# General.net
KiCad netlist of a schematic drawn in Altium Designer
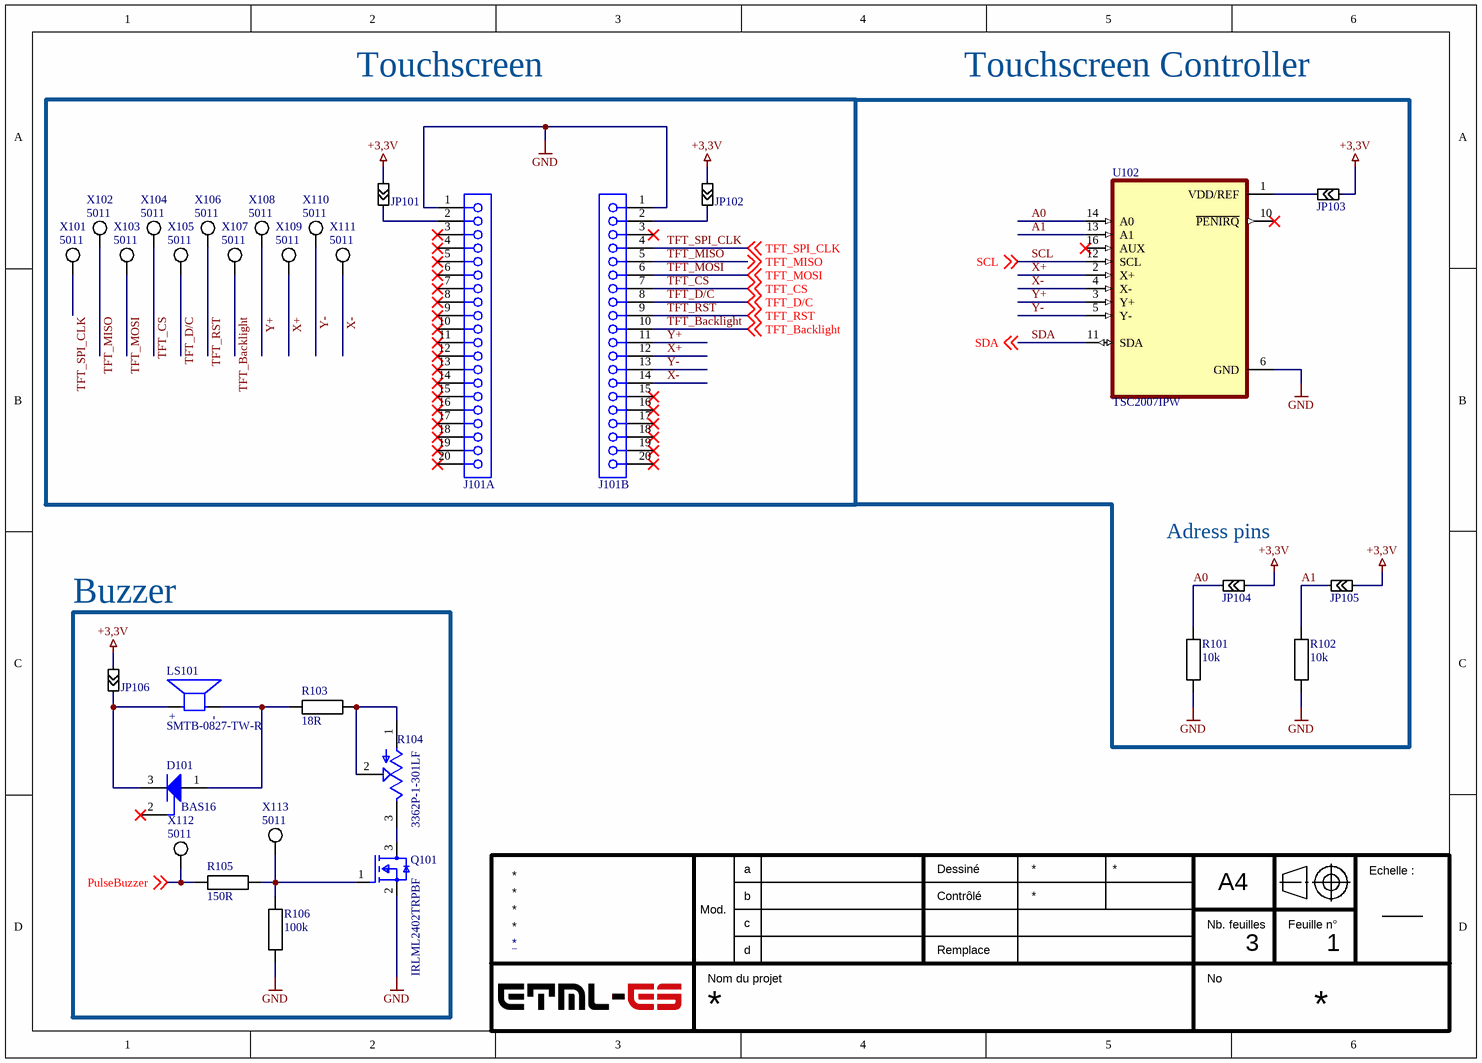
[diagram p0: General.SchDoc]

(export (version "E")
  (design (tool "Eeschema 10.0.6"))
  (components
    (comp (ref "D101")
      (value "BAS16")
      (footprint "INF-SOT23_L")
      (description "Silicon Switching Diode, SOT23, Reel, Green")
      (fields (field (name "MANUFACTURER") "Infineon"))
      (libsource (lib "Altium Content Vault") (part "INF-D_A1K3-3"))
    )
    (comp (ref "J101A")
      (value "61302011821")
      (footprint "61302011821")
      (description "WR-PHD Socket Header, THT, Vertical, pitch 2.54mm, 1 Row, 20P")
      (fields (field (name "MANUFACTURER") "Wurth Elektronik"))
      (libsource (lib "2318_Métronome_Electronique_Library") (part "61302011821"))
    )
    (comp (ref "J101B")
      (value "61302011821")
      (footprint "61302011821")
      (description "WR-PHD Socket Header, THT, Vertical, pitch 2.54mm, 1 Row, 20P")
      (fields (field (name "MANUFACTURER") "Wurth Elektronik"))
      (libsource (lib "2318_Métronome_Electronique_Library") (part "61302011821"))
    )
    (comp (ref "JP101")
      (value "Jumper Pad")
      (footprint "Jumper SMD")
      (description "SMD Jumper")
      (libsource (lib "2318_Métronome_Electronique_Library") (part "Jumper Pad"))
    )
    (comp (ref "JP102")
      (value "Jumper Pad")
      (footprint "Jumper SMD")
      (description "SMD Jumper")
      (libsource (lib "2318_Métronome_Electronique_Library") (part "Jumper Pad"))
    )
    (comp (ref "JP103")
      (value "Jumper Pad")
      (footprint "Jumper SMD")
      (description "SMD Jumper")
      (libsource (lib "2318_Métronome_Electronique_Library") (part "Jumper Pad"))
    )
    (comp (ref "JP104")
      (value "Jumper Pad")
      (footprint "Jumper SMD")
      (description "SMD Jumper")
      (libsource (lib "2318_Métronome_Electronique_Library") (part "Jumper Pad"))
    )
    (comp (ref "JP105")
      (value "Jumper Pad")
      (footprint "Jumper SMD")
      (description "SMD Jumper")
      (libsource (lib "2318_Métronome_Electronique_Library") (part "Jumper Pad"))
    )
    (comp (ref "JP106")
      (value "Jumper Pad")
      (footprint "Jumper SMD")
      (description "SMD Jumper")
      (libsource (lib "2318_Métronome_Electronique_Library") (part "Jumper Pad"))
    )
    (comp (ref "LS101")
      (value "SMTB-0827-TW-R")
      (footprint "XDCR_SMTB-0827-TW-R")
      (description "SURFACE MOUNT TRANSDUCER 3.6 V0-P")
      (fields
        (field (name "DIGI-KEY_PART_NUMBER") "668-SMTB-0827-TW-RTR-ND")
        (field (name "MF") "PUI Audio, Inc.")
      )
      (libsource (lib "2318_Métronome_Electronique_Library") (part "SMTB-0827-TW-R"))
    )
    (comp (ref "Q101")
      (value "IRLML2402TRPBF")
      (footprint "SOT95P237X112-3N")
      (description "MOSFET N-CH 20V 1.2A SOT-23")
      (libsource (lib "2318_Métronome_Electronique_Library") (part "IRLML2402TRPBF"))
    )
    (comp (ref "R101")
      (value "10k")
      (footprint "RESC2012X06M")
      (description "RES 10kohm  ±1% 0.125W 2012 (0805 INCH)")
      (fields (field (name "TOLERANCE") "±1%") (field (name "VOLTAGE") "150V"))
      (libsource (lib "ETML-ES") (part "RES"))
    )
    (comp (ref "R102")
      (value "10k")
      (footprint "RESC2012X06M")
      (description "RES 10kohm  ±1% 0.125W 2012 (0805 INCH)")
      (fields (field (name "TOLERANCE") "±1%") (field (name "VOLTAGE") "150V"))
      (libsource (lib "ETML-ES") (part "RES"))
    )
    (comp (ref "R103")
      (value "18R")
      (footprint "RESC2012X06M")
      (description "RES 18ohm  ±1% 0.125W 2012 (0805 INCH)")
      (fields (field (name "POWER") "0.125W") (field (name "TOLERANCE") "±1%"))
      (libsource (lib "ETML-ES") (part "RES"))
    )
    (comp (ref "R104")
      (value "3362P-1-301LF")
      (footprint "TRIM_3362P-1-301LF")
      (description "300 Ohms 0.5W, 1/2W PC Pins Through Hole Trimmer Potentiometer Cermet 1 Turn Top Adjustment")
      (fields (field (name "MF") "Bourns"))
      (libsource (lib "2318_Métronome_Electronique_Library") (part "3362P-1-301LF"))
    )
    (comp (ref "R105")
      (value "150R")
      (footprint "RESC2012X06M")
      (description "RES 150ohm  ±1% 0.125W 2012 (0805 INCH)")
      (fields (field (name "MANUFACTURER") "Yageo") (field (name "TOLERANCE") "±1%"))
      (libsource (lib "ETML-ES") (part "RES"))
    )
    (comp (ref "R106")
      (value "100k")
      (footprint "RESC2012X06M")
      (description "RES 100kohm  ±1% 0.125W 2012 (0805 INCH)")
      (fields (field (name "MANUFACTURER") "Yageo") (field (name "VOLTAGE") "150V"))
      (libsource (lib "ETML-ES") (part "RES"))
    )
    (comp (ref "U102")
      (value "TSC2007IPW")
      (footprint "SOP65P640X120-16N")
      (description "12-Bit, nanopower, 4-wire micro touch screen controller &nbsp; 16-TSSOP -40 to 85")
      (fields (field (name "DIGI-KEY_PART_NUMBER") "296-42398-2-ND") (field (name "MF") "Texas Instruments"))
      (libsource (lib "2318_Métronome_Electronique_Library") (part "TSC2007IPW"))
    )
    (comp (ref "X101")
      (value "5011")
      (footprint "Keystone_5011")
      (description "TEST THT MULTIPURPOSE BK")
      (fields (field (name "MANUFACTURER") "Keystone"))
      (libsource (lib "ETML-ES") (part "TEST"))
    )
    (comp (ref "X102")
      (value "5011")
      (footprint "Keystone_5011")
      (description "TEST THT MULTIPURPOSE BK")
      (fields (field (name "MANUFACTURER") "Keystone"))
      (libsource (lib "ETML-ES") (part "TEST"))
    )
    (comp (ref "X103")
      (value "5011")
      (footprint "Keystone_5011")
      (description "TEST THT MULTIPURPOSE BK")
      (fields (field (name "MANUFACTURER") "Keystone"))
      (libsource (lib "ETML-ES") (part "TEST"))
    )
    (comp (ref "X104")
      (value "5011")
      (footprint "Keystone_5011")
      (description "TEST THT MULTIPURPOSE BK")
      (fields (field (name "MANUFACTURER") "Keystone"))
      (libsource (lib "ETML-ES") (part "TEST"))
    )
    (comp (ref "X105")
      (value "5011")
      (footprint "Keystone_5011")
      (description "TEST THT MULTIPURPOSE BK")
      (fields (field (name "MANUFACTURER") "Keystone"))
      (libsource (lib "ETML-ES") (part "TEST"))
    )
    (comp (ref "X106")
      (value "5011")
      (footprint "Keystone_5011")
      (description "TEST THT MULTIPURPOSE BK")
      (fields (field (name "MANUFACTURER") "Keystone"))
      (libsource (lib "ETML-ES") (part "TEST"))
    )
    (comp (ref "X107")
      (value "5011")
      (footprint "Keystone_5011")
      (description "TEST THT MULTIPURPOSE BK")
      (fields (field (name "MANUFACTURER") "Keystone"))
      (libsource (lib "ETML-ES") (part "TEST"))
    )
    (comp (ref "X108")
      (value "5011")
      (footprint "Keystone_5011")
      (description "TEST THT MULTIPURPOSE BK")
      (fields (field (name "MANUFACTURER") "Keystone"))
      (libsource (lib "ETML-ES") (part "TEST"))
    )
    (comp (ref "X109")
      (value "5011")
      (footprint "Keystone_5011")
      (description "TEST THT MULTIPURPOSE BK")
      (fields (field (name "MANUFACTURER") "Keystone"))
      (libsource (lib "ETML-ES") (part "TEST"))
    )
    (comp (ref "X110")
      (value "5011")
      (footprint "Keystone_5011")
      (description "TEST THT MULTIPURPOSE BK")
      (fields (field (name "MANUFACTURER") "Keystone"))
      (libsource (lib "ETML-ES") (part "TEST"))
    )
    (comp (ref "X111")
      (value "5011")
      (footprint "Keystone_5011")
      (description "TEST THT MULTIPURPOSE BK")
      (fields (field (name "MANUFACTURER") "Keystone"))
      (libsource (lib "ETML-ES") (part "TEST"))
    )
    (comp (ref "X112")
      (value "5011")
      (footprint "Keystone_5011")
      (description "TEST THT MULTIPURPOSE BK")
      (fields (field (name "MANUFACTURER") "Keystone"))
      (libsource (lib "ETML-ES") (part "TEST"))
    )
    (comp (ref "X113")
      (value "5011")
      (footprint "Keystone_5011")
      (description "TEST THT MULTIPURPOSE BK")
      (fields (field (name "MANUFACTURER") "Keystone"))
      (libsource (lib "ETML-ES") (part "TEST"))
    )
  )
  (nets
    (net (code "1") (name "+3,3V") (class "Default")
      (node (ref "JP101") (pin "2") (pinfunction "2_2") (pintype "passive"))
      (node (ref "JP102") (pin "2") (pinfunction "2_2") (pintype "passive"))
      (node (ref "JP103") (pin "2") (pinfunction "2_2") (pintype "passive"))
      (node (ref "JP104") (pin "2") (pinfunction "2_2") (pintype "passive"))
      (node (ref "JP105") (pin "2") (pinfunction "2_2") (pintype "passive"))
      (node (ref "JP106") (pin "2") (pinfunction "2_2") (pintype "passive"))
    )
    (net (code "2") (name "/A0") (class "Default")
      (node (ref "JP104") (pin "1") (pinfunction "1_1") (pintype "passive"))
      (node (ref "R101") (pin "2") (pinfunction "2_2") (pintype "passive"))
      (node (ref "U102") (pin "14") (pinfunction "A0_14") (pintype "input"))
    )
    (net (code "3") (name "/A1") (class "Default")
      (node (ref "JP105") (pin "1") (pinfunction "1_1") (pintype "passive"))
      (node (ref "R102") (pin "2") (pinfunction "2_2") (pintype "passive"))
      (node (ref "U102") (pin "13") (pinfunction "A1_13") (pintype "input"))
    )
    (net (code "4") (name "/X+") (class "Default")
      (node (ref "J101B") (pin "12") (pinfunction "12_12") (pintype "passive"))
      (node (ref "U102") (pin "2") (pinfunction "X+_2") (pintype "input"))
      (node (ref "X109") (pin "1") (pinfunction "TP_1") (pintype "passive"))
    )
    (net (code "5") (name "/X-") (class "Default")
      (node (ref "J101B") (pin "14") (pinfunction "14_14") (pintype "passive"))
      (node (ref "U102") (pin "4") (pinfunction "X-_4") (pintype "input"))
      (node (ref "X111") (pin "1") (pinfunction "TP_1") (pintype "passive"))
    )
    (net (code "6") (name "/Y+") (class "Default")
      (node (ref "J101B") (pin "11") (pinfunction "11_11") (pintype "passive"))
      (node (ref "U102") (pin "3") (pinfunction "Y+_3") (pintype "input"))
      (node (ref "X108") (pin "1") (pinfunction "TP_1") (pintype "passive"))
    )
    (net (code "7") (name "/Y-") (class "Default")
      (node (ref "J101B") (pin "13") (pinfunction "13_13") (pintype "passive"))
      (node (ref "U102") (pin "5") (pinfunction "Y-_5") (pintype "input"))
      (node (ref "X110") (pin "1") (pinfunction "TP_1") (pintype "passive"))
    )
    (net (code "8") (name "GND") (class "Default")
      (node (ref "J101A") (pin "1") (pinfunction "1_1") (pintype "passive"))
      (node (ref "J101B") (pin "1") (pinfunction "1_1") (pintype "passive"))
      (node (ref "Q101") (pin "2") (pinfunction "S_2") (pintype "passive"))
      (node (ref "R101") (pin "1") (pinfunction "1_1") (pintype "passive"))
      (node (ref "R102") (pin "1") (pinfunction "1_1") (pintype "passive"))
      (node (ref "R106") (pin "1") (pinfunction "1_1") (pintype "passive"))
      (node (ref "U102") (pin "6") (pinfunction "GND_6") (pintype "power_in"))
    )
    (net (code "9") (name "Net-(D101-A)") (class "Default")
      (node (ref "D101") (pin "1") (pinfunction "A_1") (pintype "passive"))
      (node (ref "LS101") (pin "N") (pinfunction "NEG_N") (pintype "passive"))
      (node (ref "R103") (pin "2") (pinfunction "2_2") (pintype "passive"))
    )
    (net (code "10") (name "Net-(D101-K)") (class "Default")
      (node (ref "D101") (pin "3") (pinfunction "K_3") (pintype "passive"))
      (node (ref "JP106") (pin "1") (pinfunction "1_1") (pintype "passive"))
      (node (ref "LS101") (pin "P") (pinfunction "POS_P") (pintype "passive"))
    )
    (net (code "11") (name "Net-(J101A-Pad2)") (class "Default")
      (node (ref "J101A") (pin "2") (pinfunction "2_2") (pintype "passive"))
      (node (ref "JP101") (pin "1") (pinfunction "1_1") (pintype "passive"))
    )
    (net (code "12") (name "Net-(J101B-Pad2)") (class "Default")
      (node (ref "J101B") (pin "2") (pinfunction "2_2") (pintype "passive"))
      (node (ref "JP102") (pin "1") (pinfunction "1_1") (pintype "passive"))
    )
    (net (code "13") (name "Net-(Q101-D)") (class "Default")
      (node (ref "Q101") (pin "3") (pinfunction "D_3") (pintype "passive"))
      (node (ref "R104") (pin "3") (pinfunction "CW_3") (pintype "passive"))
    )
    (net (code "14") (name "Net-(Q101-G)") (class "Default")
      (node (ref "Q101") (pin "1") (pinfunction "G_1") (pintype "passive"))
      (node (ref "R105") (pin "2") (pinfunction "2_2") (pintype "passive"))
      (node (ref "R106") (pin "2") (pinfunction "2_2") (pintype "passive"))
      (node (ref "X113") (pin "1") (pinfunction "TP_1") (pintype "passive"))
    )
    (net (code "15") (name "Net-(R104-CCW)") (class "Default")
      (node (ref "R103") (pin "1") (pinfunction "1_1") (pintype "passive"))
      (node (ref "R104") (pin "1") (pinfunction "CCW_1") (pintype "passive"))
      (node (ref "R104") (pin "2") (pinfunction "WIPER_2") (pintype "passive"))
    )
    (net (code "16") (name "Net-(U102-VDD{slash}REF)") (class "Default")
      (node (ref "JP103") (pin "1") (pinfunction "1_1") (pintype "passive"))
      (node (ref "U102") (pin "1") (pinfunction "VDD/REF_1") (pintype "power_in"))
    )
    (net (code "17") (name "PulseBuzzer") (class "Default")
      (node (ref "R105") (pin "1") (pinfunction "1_1") (pintype "passive"))
      (node (ref "X112") (pin "1") (pinfunction "TP_1") (pintype "passive"))
    )
    (net (code "18") (name "SCL") (class "Default")
      (node (ref "U102") (pin "12") (pinfunction "SCL_12") (pintype "input"))
    )
    (net (code "19") (name "SDA") (class "Default")
      (node (ref "U102") (pin "11") (pinfunction "SDA_11") (pintype "bidirectional"))
    )
    (net (code "20") (name "TFT_Backlight") (class "Default")
      (node (ref "J101B") (pin "10") (pinfunction "10_10") (pintype "passive"))
      (node (ref "X107") (pin "1") (pinfunction "TP_1") (pintype "passive"))
    )
    (net (code "21") (name "TFT_CS") (class "Default")
      (node (ref "J101B") (pin "7") (pinfunction "7_7") (pintype "passive"))
      (node (ref "X104") (pin "1") (pinfunction "TP_1") (pintype "passive"))
    )
    (net (code "22") (name "TFT_D{slash}C") (class "Default")
      (node (ref "J101B") (pin "8") (pinfunction "8_8") (pintype "passive"))
      (node (ref "X105") (pin "1") (pinfunction "TP_1") (pintype "passive"))
    )
    (net (code "23") (name "TFT_MISO") (class "Default")
      (node (ref "J101B") (pin "5") (pinfunction "5_5") (pintype "passive"))
      (node (ref "X102") (pin "1") (pinfunction "TP_1") (pintype "passive"))
    )
    (net (code "24") (name "TFT_MOSI") (class "Default")
      (node (ref "J101B") (pin "6") (pinfunction "6_6") (pintype "passive"))
      (node (ref "X103") (pin "1") (pinfunction "TP_1") (pintype "passive"))
    )
    (net (code "25") (name "TFT_RST") (class "Default")
      (node (ref "J101B") (pin "9") (pinfunction "9_9") (pintype "passive"))
      (node (ref "X106") (pin "1") (pinfunction "TP_1") (pintype "passive"))
    )
    (net (code "26") (name "TFT_SPI_CLK") (class "Default")
      (node (ref "J101B") (pin "4") (pinfunction "4_4") (pintype "passive"))
      (node (ref "X101") (pin "1") (pinfunction "TP_1") (pintype "passive"))
    )
    (net (code "27") (name "unconnected-(D101-NC-Pad2)") (class "Default")
      (node (ref "D101") (pin "2") (pinfunction "NC_2") (pintype "passive+no_connect"))
    )
    (net (code "28") (name "unconnected-(J101A-Pad3)") (class "Default")
      (node (ref "J101A") (pin "3") (pinfunction "3_3") (pintype "passive+no_connect"))
    )
    (net (code "29") (name "unconnected-(J101A-Pad4)") (class "Default")
      (node (ref "J101A") (pin "4") (pinfunction "4_4") (pintype "passive+no_connect"))
    )
    (net (code "30") (name "unconnected-(J101A-Pad5)") (class "Default")
      (node (ref "J101A") (pin "5") (pinfunction "5_5") (pintype "passive+no_connect"))
    )
    (net (code "31") (name "unconnected-(J101A-Pad6)") (class "Default")
      (node (ref "J101A") (pin "6") (pinfunction "6_6") (pintype "passive+no_connect"))
    )
    (net (code "32") (name "unconnected-(J101A-Pad7)") (class "Default")
      (node (ref "J101A") (pin "7") (pinfunction "7_7") (pintype "passive+no_connect"))
    )
    (net (code "33") (name "unconnected-(J101A-Pad8)") (class "Default")
      (node (ref "J101A") (pin "8") (pinfunction "8_8") (pintype "passive+no_connect"))
    )
    (net (code "34") (name "unconnected-(J101A-Pad9)") (class "Default")
      (node (ref "J101A") (pin "9") (pinfunction "9_9") (pintype "passive+no_connect"))
    )
    (net (code "35") (name "unconnected-(J101A-Pad10)") (class "Default")
      (node (ref "J101A") (pin "10") (pinfunction "10_10") (pintype "passive+no_connect"))
    )
    (net (code "36") (name "unconnected-(J101A-Pad11)") (class "Default")
      (node (ref "J101A") (pin "11") (pinfunction "11_11") (pintype "passive+no_connect"))
    )
    (net (code "37") (name "unconnected-(J101A-Pad12)") (class "Default")
      (node (ref "J101A") (pin "12") (pinfunction "12_12") (pintype "passive+no_connect"))
    )
    (net (code "38") (name "unconnected-(J101A-Pad13)") (class "Default")
      (node (ref "J101A") (pin "13") (pinfunction "13_13") (pintype "passive+no_connect"))
    )
    (net (code "39") (name "unconnected-(J101A-Pad14)") (class "Default")
      (node (ref "J101A") (pin "14") (pinfunction "14_14") (pintype "passive+no_connect"))
    )
    (net (code "40") (name "unconnected-(J101A-Pad15)") (class "Default")
      (node (ref "J101A") (pin "15") (pinfunction "15_15") (pintype "passive+no_connect"))
    )
    (net (code "41") (name "unconnected-(J101A-Pad16)") (class "Default")
      (node (ref "J101A") (pin "16") (pinfunction "16_16") (pintype "passive+no_connect"))
    )
    (net (code "42") (name "unconnected-(J101A-Pad17)") (class "Default")
      (node (ref "J101A") (pin "17") (pinfunction "17_17") (pintype "passive+no_connect"))
    )
    (net (code "43") (name "unconnected-(J101A-Pad18)") (class "Default")
      (node (ref "J101A") (pin "18") (pinfunction "18_18") (pintype "passive+no_connect"))
    )
    (net (code "44") (name "unconnected-(J101A-Pad19)") (class "Default")
      (node (ref "J101A") (pin "19") (pinfunction "19_19") (pintype "passive+no_connect"))
    )
    (net (code "45") (name "unconnected-(J101A-Pad20)") (class "Default")
      (node (ref "J101A") (pin "20") (pinfunction "20_20") (pintype "passive+no_connect"))
    )
    (net (code "46") (name "unconnected-(J101B-Pad3)") (class "Default")
      (node (ref "J101B") (pin "3") (pinfunction "3_3") (pintype "passive+no_connect"))
    )
    (net (code "47") (name "unconnected-(J101B-Pad15)") (class "Default")
      (node (ref "J101B") (pin "15") (pinfunction "15_15") (pintype "passive+no_connect"))
    )
    (net (code "48") (name "unconnected-(J101B-Pad16)") (class "Default")
      (node (ref "J101B") (pin "16") (pinfunction "16_16") (pintype "passive+no_connect"))
    )
    (net (code "49") (name "unconnected-(J101B-Pad17)") (class "Default")
      (node (ref "J101B") (pin "17") (pinfunction "17_17") (pintype "passive+no_connect"))
    )
    (net (code "50") (name "unconnected-(J101B-Pad18)") (class "Default")
      (node (ref "J101B") (pin "18") (pinfunction "18_18") (pintype "passive+no_connect"))
    )
    (net (code "51") (name "unconnected-(J101B-Pad19)") (class "Default")
      (node (ref "J101B") (pin "19") (pinfunction "19_19") (pintype "passive+no_connect"))
    )
    (net (code "52") (name "unconnected-(J101B-Pad20)") (class "Default")
      (node (ref "J101B") (pin "20") (pinfunction "20_20") (pintype "passive+no_connect"))
    )
    (net (code "53") (name "unconnected-(U102-AUX-Pad16)") (class "Default")
      (node (ref "U102") (pin "16") (pinfunction "AUX_16") (pintype "input+no_connect"))
    )
    (net (code "54") (name "unconnected-(U102-~{PENIRQ}-Pad10)") (class "Default")
      (node (ref "U102") (pin "10") (pinfunction "~{PENIRQ}_10") (pintype "output+no_connect"))
    )
  )
)
